# Proc.net
KiCad netlist of a schematic drawn in Altium Designer
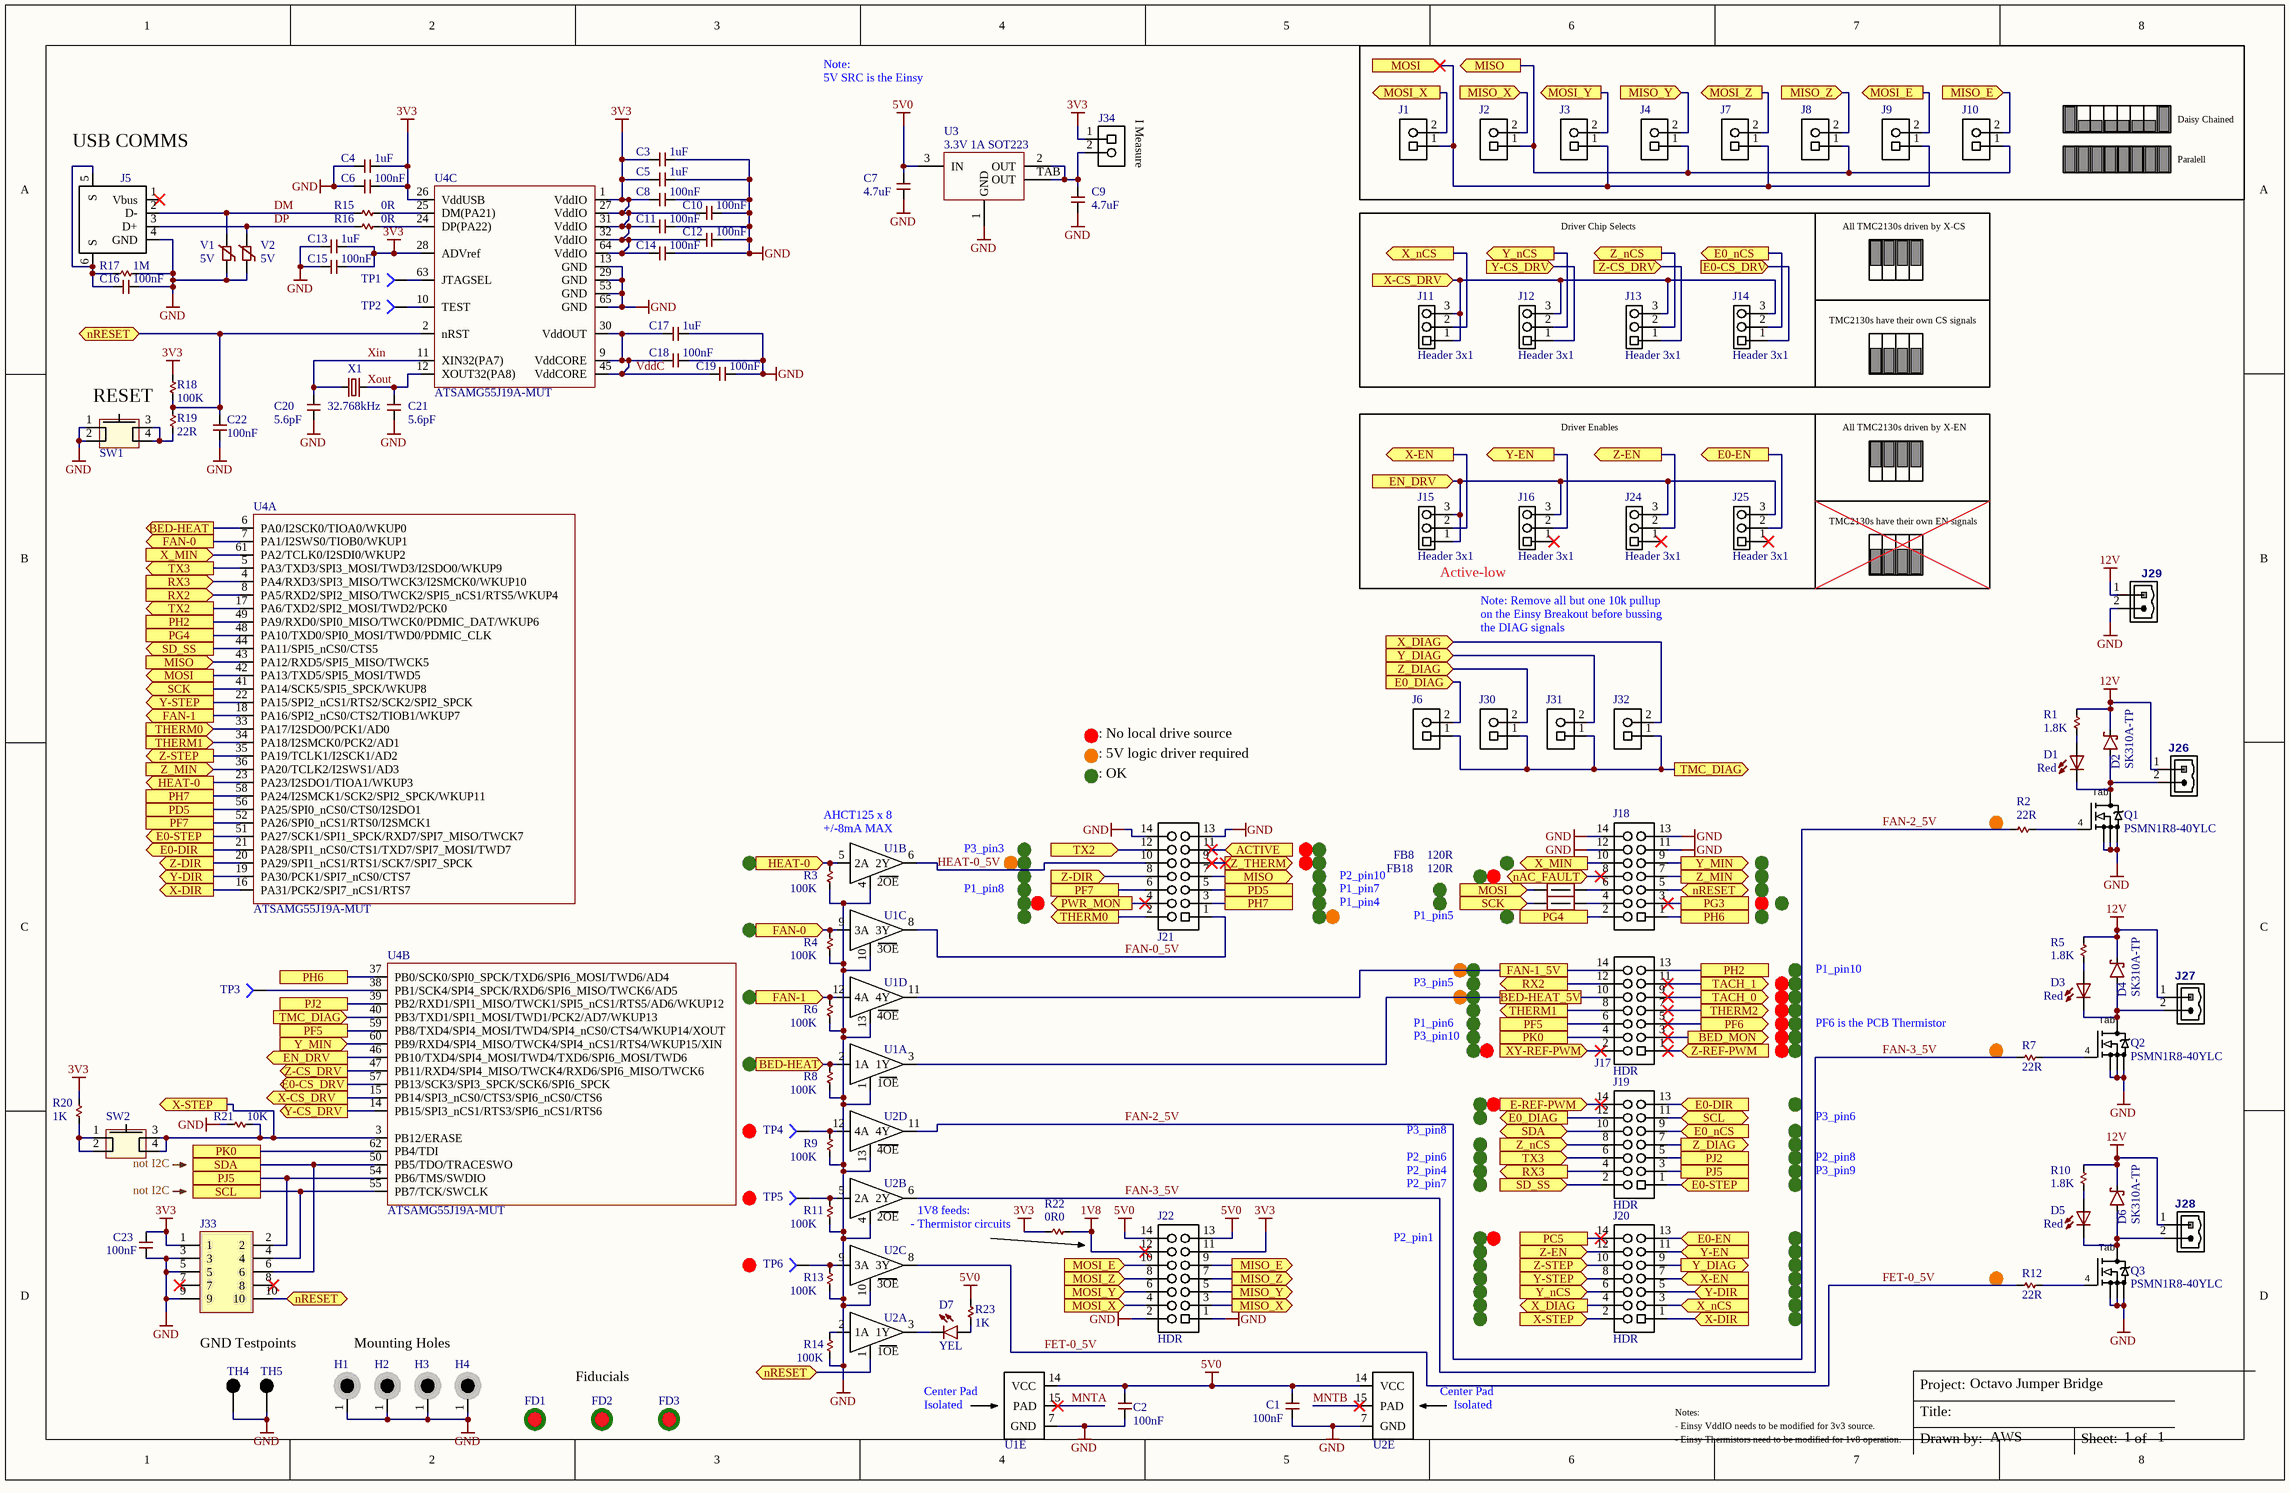
[diagram p0: Proc.SchDoc]

(export (version "E")
  (design (tool "Eeschema 10.0.6"))
  (components
    (comp (ref "C1")
      (value "100nF")
      (footprint "C0603")
      (description "CAP CER 0603 100nF 50V 10% X7R")
      (fields (field (name "MANUFACTURER") "Kemet") (field (name "PART") "100nF 50V X7R 0603"))
      (libsource (lib "Capacitors") (part "100nF 0603 50V X7R"))
    )
    (comp (ref "C2")
      (value "100nF")
      (footprint "C0603")
      (description "CAP CER 0603 100nF 50V 10% X7R")
      (fields (field (name "MANUFACTURER") "Kemet") (field (name "PART") "100nF 50V X7R 0603"))
      (libsource (lib "Capacitors") (part "100nF 0603 50V X7R"))
    )
    (comp (ref "C3")
      (value "1uF")
      (footprint "C0402")
      (description "CAP CER 0402 1uF 6.3V 10% X5R")
      (fields (field (name "MANUFACTURER") "Murata") (field (name "PART") "1uF 6.3V X5R 0402"))
      (libsource (lib "Capacitors") (part "1uF 0402 6.3V X5R"))
    )
    (comp (ref "C4")
      (value "1uF")
      (footprint "C0402")
      (description "CAP CER 0402 1uF 6.3V 10% X5R")
      (fields (field (name "MANUFACTURER") "Murata") (field (name "PART") "1uF 6.3V X5R 0402"))
      (libsource (lib "Capacitors") (part "1uF 0402 6.3V X5R"))
    )
    (comp (ref "C5")
      (value "1uF")
      (footprint "C0402")
      (description "CAP CER 0402 1uF 6.3V 10% X5R")
      (fields (field (name "MANUFACTURER") "Murata") (field (name "PART") "1uF 6.3V X5R 0402"))
      (libsource (lib "Capacitors") (part "1uF 0402 6.3V X5R"))
    )
    (comp (ref "C6")
      (value "100nF")
      (footprint "C0402")
      (description "CAP CER 0402 100nF 16V 10% X7R")
      (fields (field (name "MANUFACTURER") "Murata") (field (name "PART") "0.1uF 16V X7R 0402"))
      (libsource (lib "Capacitors") (part "100nF 0402 16V X7R"))
    )
    (comp (ref "C7")
      (value "4.7uF")
      (footprint "C0603")
      (description "CAP CER 4.7UF 6.3V X7R 0603")
      (fields (field (name "MANUFACTURER") "Samsung") (field (name "TOLERANCE") "10%"))
      (libsource (lib "Capacitors") (part "4.7uF 0603 6.3V X7R"))
    )
    (comp (ref "C8")
      (value "100nF")
      (footprint "C0402")
      (description "CAP CER 0402 100nF 16V 10% X7R")
      (fields (field (name "MANUFACTURER") "Murata") (field (name "PART") "0.1uF 16V X7R 0402"))
      (libsource (lib "Capacitors") (part "100nF 0402 16V X7R"))
    )
    (comp (ref "C9")
      (value "4.7uF")
      (footprint "C0603")
      (description "CAP CER 4.7UF 6.3V X7R 0603")
      (fields (field (name "MANUFACTURER") "Samsung") (field (name "TOLERANCE") "10%"))
      (libsource (lib "Capacitors") (part "4.7uF 0603 6.3V X7R"))
    )
    (comp (ref "C10")
      (value "100nF")
      (footprint "C0402")
      (description "CAP CER 0402 100nF 16V 10% X7R")
      (fields (field (name "MANUFACTURER") "Murata") (field (name "PART") "0.1uF 16V X7R 0402"))
      (libsource (lib "Capacitors") (part "100nF 0402 16V X7R"))
    )
    (comp (ref "C11")
      (value "100nF")
      (footprint "C0402")
      (description "CAP CER 0402 100nF 16V 10% X7R")
      (fields (field (name "MANUFACTURER") "Murata") (field (name "PART") "0.1uF 16V X7R 0402"))
      (libsource (lib "Capacitors") (part "100nF 0402 16V X7R"))
    )
    (comp (ref "C12")
      (value "100nF")
      (footprint "C0402")
      (description "CAP CER 0402 100nF 16V 10% X7R")
      (fields (field (name "MANUFACTURER") "Murata") (field (name "PART") "0.1uF 16V X7R 0402"))
      (libsource (lib "Capacitors") (part "100nF 0402 16V X7R"))
    )
    (comp (ref "C13")
      (value "1uF")
      (footprint "C0402")
      (description "CAP CER 0402 1uF 6.3V 10% X5R")
      (fields (field (name "MANUFACTURER") "Murata") (field (name "PART") "1uF 6.3V X5R 0402"))
      (libsource (lib "Capacitors") (part "1uF 0402 6.3V X5R"))
    )
    (comp (ref "C14")
      (value "100nF")
      (footprint "C0402")
      (description "CAP CER 0402 100nF 16V 10% X7R")
      (fields (field (name "MANUFACTURER") "Murata") (field (name "PART") "0.1uF 16V X7R 0402"))
      (libsource (lib "Capacitors") (part "100nF 0402 16V X7R"))
    )
    (comp (ref "C15")
      (value "100nF")
      (footprint "C0402")
      (description "CAP CER 0402 100nF 16V 10% X7R")
      (fields (field (name "MANUFACTURER") "Murata") (field (name "PART") "0.1uF 16V X7R 0402"))
      (libsource (lib "Capacitors") (part "100nF 0402 16V X7R"))
    )
    (comp (ref "C16")
      (value "100nF")
      (footprint "C0402")
      (description "CAP CER 0402 100nF 16V 10% X7R")
      (fields (field (name "MANUFACTURER") "Murata") (field (name "PART") "0.1uF 16V X7R 0402"))
      (libsource (lib "Capacitors") (part "100nF 0402 16V X7R"))
    )
    (comp (ref "C17")
      (value "1uF")
      (footprint "C0402")
      (description "CAP CER 0402 1uF 6.3V 10% X5R")
      (fields (field (name "MANUFACTURER") "Murata") (field (name "PART") "1uF 6.3V X5R 0402"))
      (libsource (lib "Capacitors") (part "1uF 0402 6.3V X5R"))
    )
    (comp (ref "C18")
      (value "100nF")
      (footprint "C0402")
      (description "CAP CER 0402 100nF 16V 10% X7R")
      (fields (field (name "MANUFACTURER") "Murata") (field (name "PART") "0.1uF 16V X7R 0402"))
      (libsource (lib "Capacitors") (part "100nF 0402 16V X7R"))
    )
    (comp (ref "C19")
      (value "100nF")
      (footprint "C0402")
      (description "CAP CER 0402 100nF 16V 10% X7R")
      (fields (field (name "MANUFACTURER") "Murata") (field (name "PART") "0.1uF 16V X7R 0402"))
      (libsource (lib "Capacitors") (part "100nF 0402 16V X7R"))
    )
    (comp (ref "C20")
      (value "5.6pF")
      (footprint "C0402")
      (description "CAP CER 5.6PF 50V C0G/NP0 0402")
      (fields (field (name "MANUFACTURER") "Murata") (field (name "PART") "5.6pF 50V 0402 C0G"))
      (libsource (lib "Capacitors") (part "5.6pF 50V 0402 C0G"))
    )
    (comp (ref "C21")
      (value "5.6pF")
      (footprint "C0402")
      (description "CAP CER 5.6PF 50V C0G/NP0 0402")
      (fields (field (name "MANUFACTURER") "Murata") (field (name "PART") "5.6pF 50V 0402 C0G"))
      (libsource (lib "Capacitors") (part "5.6pF 50V 0402 C0G"))
    )
    (comp (ref "C22")
      (value "100nF")
      (footprint "C0402")
      (description "CAP CER 0402 100nF 16V 10% X7R")
      (fields (field (name "MANUFACTURER") "Murata") (field (name "PART") "0.1uF 16V X7R 0402"))
      (libsource (lib "Capacitors") (part "100nF 0402 16V X7R"))
    )
    (comp (ref "C23")
      (value "100nF")
      (footprint "C0402")
      (description "CAP CER 0402 100nF 16V 10% X7R")
      (fields (field (name "MANUFACTURER") "Murata") (field (name "PART") "0.1uF 16V X7R 0402"))
      (libsource (lib "Capacitors") (part "100nF 0402 16V X7R"))
    )
    (comp (ref "D1")
      (value "Red")
      (footprint "LED2012120")
      (description "LED 0805 Red")
      (fields (field (name "MANUFACTURER") "Dialight") (field (name "PART") "LED Red 0805"))
      (libsource (lib "LEDs") (part "5988110107F"))
    )
    (comp (ref "D2")
      (value "SK310A-TP")
      (footprint "SMA-SM")
      (description "DIODE Schottky 3A SMA")
      (fields (field (name "MANUFACTURER") "MCC") (field (name "PART") "Schottky Diode 100V 3A"))
      (libsource (lib "Diodes") (part "SK310A"))
    )
    (comp (ref "D3")
      (value "Red")
      (footprint "LED2012120")
      (description "LED 0805 Red")
      (fields (field (name "MANUFACTURER") "Dialight") (field (name "PART") "LED Red 0805"))
      (libsource (lib "LEDs") (part "5988110107F"))
    )
    (comp (ref "D4")
      (value "SK310A-TP")
      (footprint "SMA-SM")
      (description "DIODE Schottky 3A SMA")
      (fields (field (name "MANUFACTURER") "MCC") (field (name "PART") "Schottky Diode 100V 3A"))
      (libsource (lib "Diodes") (part "SK310A"))
    )
    (comp (ref "D5")
      (value "Red")
      (footprint "LED2012120")
      (description "LED 0805 Red")
      (fields (field (name "MANUFACTURER") "Dialight") (field (name "PART") "LED Red 0805"))
      (libsource (lib "LEDs") (part "5988110107F"))
    )
    (comp (ref "D6")
      (value "SK310A-TP")
      (footprint "SMA-SM")
      (description "DIODE Schottky 3A SMA")
      (fields (field (name "MANUFACTURER") "MCC") (field (name "PART") "Schottky Diode 100V 3A"))
      (libsource (lib "Diodes") (part "SK310A"))
    )
    (comp (ref "D7")
      (value "YEL")
      (footprint "LED2012120")
      (description "LED 0805 Yellow")
      (fields (field (name "MANUFACTURER") "Dialight") (field (name "PART") "LED Yellow 0805"))
      (libsource (lib "LEDs") (part "5988140107F"))
    )
    (comp (ref "FB8")
      (value "120R")
      (footprint "R0402")
      (description "FERRITE BEAD 120 OHM 0402 1LN")
      (fields (field (name "MANUFACTURER") "Taiyo Yuden") (field (name "PART") "FERRITE 120R 1A 0402"))
      (libsource (lib "Inductors") (part "FERRITE 120R 1A 0402"))
    )
    (comp (ref "FB18")
      (value "120R")
      (footprint "R0402")
      (description "FERRITE BEAD 120 OHM 0402 1LN")
      (fields (field (name "MANUFACTURER") "Taiyo Yuden") (field (name "PART") "FERRITE 120R 1A 0402"))
      (libsource (lib "Inductors") (part "FERRITE 120R 1A 0402"))
    )
    (comp (ref "FD1")
      (value "FIDUCIAL")
      (footprint "FIDUCIAL-1X2")
      (libsource (lib "MISC") (part "FIDUCIAL"))
    )
    (comp (ref "FD2")
      (value "FIDUCIAL")
      (footprint "FIDUCIAL-1X2")
      (libsource (lib "MISC") (part "FIDUCIAL"))
    )
    (comp (ref "FD3")
      (value "FIDUCIAL")
      (footprint "FIDUCIAL-1X2")
      (libsource (lib "MISC") (part "FIDUCIAL"))
    )
    (comp (ref "H1")
      (value "Hole_DS")
      (footprint "Wave_hole_3x7-doubleSided")
      (libsource (lib "MISC") (part "Hole_DS"))
    )
    (comp (ref "H2")
      (value "Hole_DS")
      (footprint "Wave_hole_3x7-doubleSided")
      (libsource (lib "MISC") (part "Hole_DS"))
    )
    (comp (ref "H3")
      (value "Hole_DS")
      (footprint "Wave_hole_3x7-doubleSided")
      (libsource (lib "MISC") (part "Hole_DS"))
    )
    (comp (ref "H4")
      (value "Hole_DS")
      (footprint "Wave_hole_3x7-doubleSided")
      (libsource (lib "MISC") (part "Hole_DS"))
    )
    (comp (ref "J1")
      (value "Header 2x1")
      (footprint "HDR2X1")
      (description "Header 2Pin 1Row T-Hole")
      (fields (field (name "MANUFACTURER") "Multicomp") (field (name "PART") "CONN 2Pin 1Row 0.1\""))
      (libsource (lib "Connectors") (part "Header 2x1"))
    )
    (comp (ref "J2")
      (value "Header 2x1")
      (footprint "HDR2X1")
      (description "Header 2Pin 1Row T-Hole")
      (fields (field (name "MANUFACTURER") "Multicomp") (field (name "PART") "CONN 2Pin 1Row 0.1\""))
      (libsource (lib "Connectors") (part "Header 2x1"))
    )
    (comp (ref "J3")
      (value "Header 2x1")
      (footprint "HDR2X1")
      (description "Header 2Pin 1Row T-Hole")
      (fields (field (name "MANUFACTURER") "Multicomp") (field (name "PART") "CONN 2Pin 1Row 0.1\""))
      (libsource (lib "Connectors") (part "Header 2x1"))
    )
    (comp (ref "J4")
      (value "Header 2x1")
      (footprint "HDR2X1")
      (description "Header 2Pin 1Row T-Hole")
      (fields (field (name "MANUFACTURER") "Multicomp") (field (name "PART") "CONN 2Pin 1Row 0.1\""))
      (libsource (lib "Connectors") (part "Header 2x1"))
    )
    (comp (ref "J5")
      (value "USB-B TH R/A")
      (footprint "PN61729_ALT")
      (description "USB connector B PTH")
      (fields (field (name "MANUFACTURER") "FCI") (field (name "PART") "USB-B"))
      (libsource (lib "Connectors") (part "USB-B TH R/A"))
    )
    (comp (ref "J6")
      (value "Header 2x1")
      (footprint "HDR2X1")
      (description "Header 2Pin 1Row T-Hole")
      (fields (field (name "MANUFACTURER") "Multicomp") (field (name "PART") "CONN 2Pin 1Row 0.1\""))
      (libsource (lib "Connectors") (part "Header 2x1"))
    )
    (comp (ref "J7")
      (value "Header 2x1")
      (footprint "HDR2X1")
      (description "Header 2Pin 1Row T-Hole")
      (fields (field (name "MANUFACTURER") "Multicomp") (field (name "PART") "CONN 2Pin 1Row 0.1\""))
      (libsource (lib "Connectors") (part "Header 2x1"))
    )
    (comp (ref "J8")
      (value "Header 2x1")
      (footprint "HDR2X1")
      (description "Header 2Pin 1Row T-Hole")
      (fields (field (name "MANUFACTURER") "Multicomp") (field (name "PART") "CONN 2Pin 1Row 0.1\""))
      (libsource (lib "Connectors") (part "Header 2x1"))
    )
    (comp (ref "J9")
      (value "Header 2x1")
      (footprint "HDR2X1")
      (description "Header 2Pin 1Row T-Hole")
      (fields (field (name "MANUFACTURER") "Multicomp") (field (name "PART") "CONN 2Pin 1Row 0.1\""))
      (libsource (lib "Connectors") (part "Header 2x1"))
    )
    (comp (ref "J10")
      (value "Header 2x1")
      (footprint "HDR2X1")
      (description "Header 2Pin 1Row T-Hole")
      (fields (field (name "MANUFACTURER") "Multicomp") (field (name "PART") "CONN 2Pin 1Row 0.1\""))
      (libsource (lib "Connectors") (part "Header 2x1"))
    )
    (comp (ref "J11")
      (value "Header 3x1")
      (footprint "HDR3X1")
      (description "Header 3Pin 1Row T-Hole")
      (fields (field (name "MANUFACTURER") "Multicomp") (field (name "PART") "CONN 3Pin 1Row 0.1\""))
      (libsource (lib "Connectors") (part "Header 3x1 Male Pin"))
    )
    (comp (ref "J12")
      (value "Header 3x1")
      (footprint "HDR3X1")
      (description "Header 3Pin 1Row T-Hole")
      (fields (field (name "MANUFACTURER") "Multicomp") (field (name "PART") "CONN 3Pin 1Row 0.1\""))
      (libsource (lib "Connectors") (part "Header 3x1 Male Pin"))
    )
    (comp (ref "J13")
      (value "Header 3x1")
      (footprint "HDR3X1")
      (description "Header 3Pin 1Row T-Hole")
      (fields (field (name "MANUFACTURER") "Multicomp") (field (name "PART") "CONN 3Pin 1Row 0.1\""))
      (libsource (lib "Connectors") (part "Header 3x1 Male Pin"))
    )
    (comp (ref "J14")
      (value "Header 3x1")
      (footprint "HDR3X1")
      (description "Header 3Pin 1Row T-Hole")
      (fields (field (name "MANUFACTURER") "Multicomp") (field (name "PART") "CONN 3Pin 1Row 0.1\""))
      (libsource (lib "Connectors") (part "Header 3x1 Male Pin"))
    )
    (comp (ref "J15")
      (value "Header 3x1")
      (footprint "HDR3X1")
      (description "Header 3Pin 1Row T-Hole")
      (fields (field (name "MANUFACTURER") "Multicomp") (field (name "PART") "CONN 3Pin 1Row 0.1\""))
      (libsource (lib "Connectors") (part "Header 3x1 Male Pin"))
    )
    (comp (ref "J16")
      (value "Header 3x1")
      (footprint "HDR3X1")
      (description "Header 3Pin 1Row T-Hole")
      (fields (field (name "MANUFACTURER") "Multicomp") (field (name "PART") "CONN 3Pin 1Row 0.1\""))
      (libsource (lib "Connectors") (part "Header 3x1 Male Pin"))
    )
    (comp (ref "J17")
      (value "HDR")
      (footprint "HDR2X7_ALT_PINOUT")
      (description "CONN HEADER .100\" DUAL STR 14POS")
      (fields (field (name "MANUFACTURER") "Sullins") (field (name "TOLERANCE") "-NA-"))
      (libsource (lib "Connectors") (part "Header 2X7 Male Pin"))
    )
    (comp (ref "J18")
      (value "HDR")
      (footprint "HDR2X7_ALT_PINOUT")
      (description "CONN HEADER .100\" DUAL STR 14POS")
      (fields (field (name "MANUFACTURER") "Sullins") (field (name "TOLERANCE") "-NA-"))
      (libsource (lib "Connectors") (part "Header 2X7 Male Pin"))
    )
    (comp (ref "J19")
      (value "HDR")
      (footprint "HDR2X7_ALT_PINOUT")
      (description "CONN HEADER .100\" DUAL STR 14POS")
      (fields (field (name "MANUFACTURER") "Sullins") (field (name "TOLERANCE") "-NA-"))
      (libsource (lib "Connectors") (part "Header 2X7 Male Pin"))
    )
    (comp (ref "J20")
      (value "HDR")
      (footprint "HDR2X7_ALT_PINOUT")
      (description "CONN HEADER .100\" DUAL STR 14POS")
      (fields (field (name "MANUFACTURER") "Sullins") (field (name "TOLERANCE") "-NA-"))
      (libsource (lib "Connectors") (part "Header 2X7 Male Pin"))
    )
    (comp (ref "J21")
      (value "HDR")
      (footprint "HDR2X7_ALT_PINOUT")
      (description "CONN HEADER .100\" DUAL STR 14POS")
      (fields (field (name "MANUFACTURER") "Sullins") (field (name "TOLERANCE") "-NA-"))
      (libsource (lib "Connectors") (part "Header 2X7 Male Pin"))
    )
    (comp (ref "J22")
      (value "HDR")
      (footprint "HDR2X7_ALT_PINOUT")
      (description "CONN HEADER .100\" DUAL STR 14POS")
      (fields (field (name "MANUFACTURER") "Sullins") (field (name "TOLERANCE") "-NA-"))
      (libsource (lib "Connectors") (part "Header 2X7 Male Pin"))
    )
    (comp (ref "J24")
      (value "Header 3x1")
      (footprint "HDR3X1")
      (description "Header 3Pin 1Row T-Hole")
      (fields (field (name "MANUFACTURER") "Multicomp") (field (name "PART") "CONN 3Pin 1Row 0.1\""))
      (libsource (lib "Connectors") (part "Header 3x1 Male Pin"))
    )
    (comp (ref "J25")
      (value "Header 3x1")
      (footprint "HDR3X1")
      (description "Header 3Pin 1Row T-Hole")
      (fields (field (name "MANUFACTURER") "Multicomp") (field (name "PART") "CONN 3Pin 1Row 0.1\""))
      (libsource (lib "Connectors") (part "Header 3x1 Male Pin"))
    )
    (comp (ref "J26")
      (value "0395311002")
      (footprint "MSTBV2")
      (description "Conn - 5.08mm Pitch Fixed")
      (fields (field (name "MANUFACTURER") "Molex") (field (name "PART") "2POS"))
      (libsource (lib "Connectors") (part "0395311002"))
    )
    (comp (ref "J27")
      (value "0395311002")
      (footprint "MSTBV2")
      (description "Conn - 5.08mm Pitch Fixed")
      (fields (field (name "MANUFACTURER") "Molex") (field (name "PART") "2POS"))
      (libsource (lib "Connectors") (part "0395311002"))
    )
    (comp (ref "J28")
      (value "0395311002")
      (footprint "MSTBV2")
      (description "Conn - 5.08mm Pitch Fixed")
      (fields (field (name "MANUFACTURER") "Molex") (field (name "PART") "2POS"))
      (libsource (lib "Connectors") (part "0395311002"))
    )
    (comp (ref "J29")
      (value "0395311002")
      (footprint "MSTBV2")
      (description "Conn - 5.08mm Pitch Fixed")
      (fields (field (name "MANUFACTURER") "Molex") (field (name "PART") "2POS"))
      (libsource (lib "Connectors") (part "0395311002"))
    )
    (comp (ref "J30")
      (value "Header 2x1")
      (footprint "HDR2X1")
      (description "Header 2Pin 1Row T-Hole")
      (fields (field (name "MANUFACTURER") "Multicomp") (field (name "PART") "CONN 2Pin 1Row 0.1\""))
      (libsource (lib "Connectors") (part "Header 2x1"))
    )
    (comp (ref "J31")
      (value "Header 2x1")
      (footprint "HDR2X1")
      (description "Header 2Pin 1Row T-Hole")
      (fields (field (name "MANUFACTURER") "Multicomp") (field (name "PART") "CONN 2Pin 1Row 0.1\""))
      (libsource (lib "Connectors") (part "Header 2x1"))
    )
    (comp (ref "J32")
      (value "Header 2x1")
      (footprint "HDR2X1")
      (description "Header 2Pin 1Row T-Hole")
      (fields (field (name "MANUFACTURER") "Multicomp") (field (name "PART") "CONN 2Pin 1Row 0.1\""))
      (libsource (lib "Connectors") (part "Header 2x1"))
    )
    (comp (ref "J33")
      (value "0.05in 2-Row")
      (footprint "FTSH-105-XX-X-DV")
      (description "20021121-00010C4LF")
      (fields (field (name "MANUFACTURER") "Amphenol FCI") (field (name "PART") "10 Pin Conn 2Row SMT"))
      (libsource (lib "Connectors") (part "ARM Cortex JTAG-DEBUG Header"))
    )
    (comp (ref "J34")
      (value "Header 2x1")
      (footprint "HDR2X1")
      (description "Header 2Pin 1Row T-Hole")
      (fields (field (name "MANUFACTURER") "Multicomp") (field (name "PART") "CONN 2Pin 1Row 0.1\""))
      (libsource (lib "") (part "Header 2x1_1"))
    )
    (comp (ref "Q1")
      (value "PSMN1R8-40YLC")
      (footprint "SOT669")
      (description "MOSFET N-CH 40V 100A LFPAK")
      (fields (field (name "MANUFACTURER") "Nexperia") (field (name "PART") "N-FET"))
      (libsource (lib "Transistors") (part "PSMN1R8-40YLC"))
    )
    (comp (ref "Q2")
      (value "PSMN1R8-40YLC")
      (footprint "SOT669")
      (description "MOSFET N-CH 40V 100A LFPAK")
      (fields (field (name "MANUFACTURER") "Nexperia") (field (name "PART") "N-FET"))
      (libsource (lib "Transistors") (part "PSMN1R8-40YLC"))
    )
    (comp (ref "Q3")
      (value "PSMN1R8-40YLC")
      (footprint "SOT669")
      (description "MOSFET N-CH 40V 100A LFPAK")
      (fields (field (name "MANUFACTURER") "Nexperia") (field (name "PART") "N-FET"))
      (libsource (lib "Transistors") (part "PSMN1R8-40YLC"))
    )
    (comp (ref "R1")
      (value "1.8K")
      (footprint "R0603")
      (description "RES 0603 1.8K 100mW 5%")
      (fields (field (name "MANUFACTURER") "Yageo") (field (name "PART") "1.8k 5% 0603"))
      (libsource (lib "Resistors") (part "1.8k 5% 0603"))
    )
    (comp (ref "R2")
      (value "22R")
      (footprint "R0805")
      (description "RES SMD 22 OHM 1% 1/8W 0805")
      (fields (field (name "MANUFACTURER") "Yageo") (field (name "TOLERANCE") "+/- 1%"))
      (libsource (lib "Resistors") (part "22R 1% 0805"))
    )
    (comp (ref "R3")
      (value "100K")
      (footprint "Passives:R0402")
      (description "RES SMD 100K OHM 1% 1/16W 0402")
      (fields (field (name "MANUFACTURER") "Samsung") (field (name "PART") "100k 1% 0402"))
      (libsource (lib "Resistors") (part "100k 1% 0402"))
    )
    (comp (ref "R4")
      (value "100K")
      (footprint "Passives:R0402")
      (description "RES SMD 100K OHM 1% 1/16W 0402")
      (fields (field (name "MANUFACTURER") "Samsung") (field (name "PART") "100k 1% 0402"))
      (libsource (lib "Resistors") (part "100k 1% 0402"))
    )
    (comp (ref "R5")
      (value "1.8K")
      (footprint "R0603")
      (description "RES 0603 1.8K 100mW 5%")
      (fields (field (name "MANUFACTURER") "Yageo") (field (name "PART") "1.8k 5% 0603"))
      (libsource (lib "Resistors") (part "1.8k 5% 0603"))
    )
    (comp (ref "R6")
      (value "100K")
      (footprint "Passives:R0402")
      (description "RES SMD 100K OHM 1% 1/16W 0402")
      (fields (field (name "MANUFACTURER") "Samsung") (field (name "PART") "100k 1% 0402"))
      (libsource (lib "Resistors") (part "100k 1% 0402"))
    )
    (comp (ref "R7")
      (value "22R")
      (footprint "R0805")
      (description "RES SMD 22 OHM 1% 1/8W 0805")
      (fields (field (name "MANUFACTURER") "Yageo") (field (name "TOLERANCE") "+/- 1%"))
      (libsource (lib "Resistors") (part "22R 1% 0805"))
    )
    (comp (ref "R8")
      (value "100K")
      (footprint "Passives:R0402")
      (description "RES SMD 100K OHM 1% 1/16W 0402")
      (fields (field (name "MANUFACTURER") "Samsung") (field (name "PART") "100k 1% 0402"))
      (libsource (lib "Resistors") (part "100k 1% 0402"))
    )
    (comp (ref "R9")
      (value "100K")
      (footprint "Passives:R0402")
      (description "RES SMD 100K OHM 1% 1/16W 0402")
      (fields (field (name "MANUFACTURER") "Samsung") (field (name "PART") "100k 1% 0402"))
      (libsource (lib "Resistors") (part "100k 1% 0402"))
    )
    (comp (ref "R10")
      (value "1.8K")
      (footprint "R0603")
      (description "RES 0603 1.8K 100mW 5%")
      (fields (field (name "MANUFACTURER") "Yageo") (field (name "PART") "1.8k 5% 0603"))
      (libsource (lib "Resistors") (part "1.8k 5% 0603"))
    )
    (comp (ref "R11")
      (value "100K")
      (footprint "Passives:R0402")
      (description "RES SMD 100K OHM 1% 1/16W 0402")
      (fields (field (name "MANUFACTURER") "Samsung") (field (name "PART") "100k 1% 0402"))
      (libsource (lib "Resistors") (part "100k 1% 0402"))
    )
    (comp (ref "R12")
      (value "22R")
      (footprint "R0805")
      (description "RES SMD 22 OHM 1% 1/8W 0805")
      (fields (field (name "MANUFACTURER") "Yageo") (field (name "TOLERANCE") "+/- 1%"))
      (libsource (lib "Resistors") (part "22R 1% 0805"))
    )
    (comp (ref "R13")
      (value "100K")
      (footprint "Passives:R0402")
      (description "RES SMD 100K OHM 1% 1/16W 0402")
      (fields (field (name "MANUFACTURER") "Samsung") (field (name "PART") "100k 1% 0402"))
      (libsource (lib "Resistors") (part "100k 1% 0402"))
    )
    (comp (ref "R14")
      (value "100K")
      (footprint "Passives:R0402")
      (description "RES SMD 100K OHM 1% 1/16W 0402")
      (fields (field (name "MANUFACTURER") "Samsung") (field (name "PART") "100k 1% 0402"))
      (libsource (lib "Resistors") (part "100k 1% 0402"))
    )
    (comp (ref "R15")
      (value "0R")
      (footprint "R0402")
      (description "RES SMD 0.0OHM JUMPER 1/10W 0402")
      (fields (field (name "MANUFACTURER") "Panasonic") (field (name "TOLERANCE") "1%"))
      (libsource (lib "Resistors") (part "0R 0402"))
    )
    (comp (ref "R16")
      (value "0R")
      (footprint "R0402")
      (description "RES SMD 0.0OHM JUMPER 1/10W 0402")
      (fields (field (name "MANUFACTURER") "Panasonic") (field (name "TOLERANCE") "1%"))
      (libsource (lib "Resistors") (part "0R 0402"))
    )
    (comp (ref "R17")
      (value "1M")
      (footprint "Passives:R0402")
      (description "RES 0402 1M 100mW 5%")
      (fields (field (name "MANUFACTURER") "Panasonic") (field (name "PART") "1M 5% 0402"))
      (libsource (lib "Resistors") (part "1M 5% 0402"))
    )
    (comp (ref "R18")
      (value "100K")
      (footprint "Passives:R0402")
      (description "RES SMD 100K OHM 1% 1/16W 0402")
      (fields (field (name "MANUFACTURER") "Samsung") (field (name "PART") "100k 1% 0402"))
      (libsource (lib "Resistors") (part "100k 1% 0402"))
    )
    (comp (ref "R19")
      (value "22R")
      (footprint "R0805")
      (description "RES SMD 22 OHM 1% 1/8W 0805")
      (fields (field (name "MANUFACTURER") "Yageo") (field (name "TOLERANCE") "+/- 1%"))
      (libsource (lib "Resistors") (part "22R 1% 0805"))
    )
    (comp (ref "R20")
      (value "1K")
      (footprint "R0402")
      (description "RES SMD 1K OHM 1% 1/16W 0402")
      (fields (field (name "MANUFACTURER") "Yageo") (field (name "PART") "1k"))
      (libsource (lib "3Delight") (part "RC0402FR-071KL"))
    )
    (comp (ref "R21")
      (value "10K")
      (footprint "R0402")
      (description "RES SMD 10K OHM 1% 1/16W 0402")
      (fields (field (name "MANUFACTURER") "Yageo") (field (name "PART") "10k 1% 0402"))
      (libsource (lib "Resistors") (part "10k 1% 0402"))
    )
    (comp (ref "R22")
      (value "0R0")
      (footprint "R0805")
      (description "RES 0.0 OHM 1/8W JUMP 0805 SMD")
      (fields (field (name "MANUFACTURER") "STACKPOLE") (field (name "TOLERANCE") "1%"))
      (libsource (lib "Resistors") (part "0R0 1% 0805"))
    )
    (comp (ref "R23")
      (value "1K")
      (footprint "R0402")
      (description "RES SMD 1K OHM 1% 1/16W 0402")
      (fields (field (name "MANUFACTURER") "Yageo") (field (name "PART") "1k"))
      (libsource (lib "3Delight") (part "RC0402FR-071KL"))
    )
    (comp (ref "SW1")
      (value "KMR741NG ULC LFS")
      (footprint "KMR 6 Series")
      (description "SWITCH TACTILE SPST-NO 0.05A 12V")
      (fields (field (name "MANUFACTURER") "C&K") (field (name "PART") "Tactile Pushbutton SMT"))
      (libsource (lib "Switches") (part "KMR741NG ULC LFS"))
    )
    (comp (ref "SW2")
      (value "KMR741NG ULC LFS")
      (footprint "KMR 6 Series")
      (description "SWITCH TACTILE SPST-NO 0.05A 12V")
      (fields (field (name "MANUFACTURER") "C&K") (field (name "PART") "Tactile Pushbutton SMT"))
      (libsource (lib "Switches") (part "KMR741NG ULC LFS"))
    )
    (comp (ref "TH4")
      (value "TH")
      (footprint "TP_80_150")
      (description "THRUHOLE 85mil")
      (fields (field (name "PART") "THRUHOLE"))
      (libsource (lib "Connectors") (part "TH 85mil"))
    )
    (comp (ref "TH5")
      (value "TH")
      (footprint "TP_80_150")
      (description "THRUHOLE 85mil")
      (fields (field (name "PART") "THRUHOLE"))
      (libsource (lib "Connectors") (part "TH 85mil"))
    )
    (comp (ref "TP1")
      (value "NOTAPART-Testpoint")
      (footprint "TP-2")
      (description "Testpoint SMT")
      (libsource (lib "Connectors") (part "Testpoint SMT"))
    )
    (comp (ref "TP2")
      (value "NOTAPART-Testpoint")
      (footprint "TP-2")
      (description "Testpoint SMT")
      (libsource (lib "Connectors") (part "Testpoint SMT"))
    )
    (comp (ref "TP3")
      (value "NOTAPART-Testpoint")
      (footprint "TP-2")
      (description "Testpoint SMT")
      (libsource (lib "Connectors") (part "Testpoint SMT"))
    )
    (comp (ref "TP4")
      (value "NOTAPART-Testpoint")
      (footprint "TP-2")
      (description "Testpoint SMT")
      (libsource (lib "Connectors") (part "Testpoint SMT"))
    )
    (comp (ref "TP5")
      (value "NOTAPART-Testpoint")
      (footprint "TP-2")
      (description "Testpoint SMT")
      (libsource (lib "Connectors") (part "Testpoint SMT"))
    )
    (comp (ref "TP6")
      (value "NOTAPART-Testpoint")
      (footprint "TP-2")
      (description "Testpoint SMT")
      (libsource (lib "Connectors") (part "Testpoint SMT"))
    )
    (comp (ref "U1")
      (value "SN74AHCT125RGYR")
      (footprint "QFN50P350X350X100_RGY_S-PVQFN-N14")
      (description "Quadruple Bus Buffer Gates With 3-State Outputs 14-VQFN -40 to 125")
      (fields
        (field (name "MANUFACTURER") "Texas Instruments")
        (field (name "PART") "IC BUS BUFFER TRI-ST QD 14VQFN")
      )
      (libsource (lib "ICs-Logic") (part "SN74AHCT125"))
    )
    (comp (ref "U2")
      (value "SN74AHCT125RGYR")
      (footprint "QFN50P350X350X100_RGY_S-PVQFN-N14")
      (description "Quadruple Bus Buffer Gates With 3-State Outputs 14-VQFN -40 to 125")
      (fields
        (field (name "MANUFACTURER") "Texas Instruments")
        (field (name "PART") "IC BUS BUFFER TRI-ST QD 14VQFN")
      )
      (libsource (lib "ICs-Logic") (part "SN74AHCT125"))
    )
    (comp (ref "U3")
      (value "3.3V 1A SOT223")
      (footprint "SOT223_AZ1117")
      (description "IC REG LDO 3.3V 1A SOT223")
      (fields (field (name "MANUFACTURER") "Diodes Inc") (field (name "TOLERANCE") "-NA-"))
      (libsource (lib "ICs-Power") (part "LDO 3.3V 1A SOT223"))
    )
    (comp (ref "U4")
      (value "ATSAMG55J19A-MUT")
      (footprint "QFN64_7.5x7.5mm")
      (description "IC MCU 32BIT 512KB FLASH 64QFN")
      (fields (field (name "MANUFACTURER") "Atmel") (field (name "TOLERANCE") "-NA-"))
      (libsource (lib "ICs-uC") (part "ATSAMG55J19A-MUT"))
    )
    (comp (ref "V1")
      (value "5V")
      (footprint "R0603")
      (description "VAR 0603 5V 0.5Pf")
      (fields (field (name "MANUFACTURER") "YAGEO") (field (name "PART") "5VDC"))
      (libsource (lib "ESD") (part "VAR 5V 0603"))
    )
    (comp (ref "V2")
      (value "5V")
      (footprint "R0603")
      (description "VAR 0603 5V 0.5Pf")
      (fields (field (name "MANUFACTURER") "YAGEO") (field (name "PART") "5VDC"))
      (libsource (lib "ESD") (part "VAR 5V 0603"))
    )
    (comp (ref "X1")
      (value "32.768kHz")
      (footprint "XTAL_32X15_2")
      (description "CRYSTAL 32.768KHZ 7PF SMD")
      (fields (field (name "MANUFACTURER") "ECS") (field (name "TOLERANCE") "20ppm"))
      (libsource (lib "XTAL") (part "32.768kHz 20ppm 7pF 50k_ESR"))
    )
  )
  (nets
    (net (code "1") (name "/ACTIVE") (class "Default")
      (node (ref "J21") (pin "11") (pinfunction "11_11") (pintype "passive+no_connect"))
    )
    (net (code "2") (name "/BED-HEAT") (class "Default")
      (node (ref "R8") (pin "1") (pinfunction "1_1") (pintype "passive"))
      (node (ref "U1") (pin "2") (pinfunction "1A_2") (pintype "passive"))
      (node (ref "U4") (pin "6") (pinfunction "PA0/I2SCK0/TIOA0/WKUP0_6") (pintype "passive"))
    )
    (net (code "3") (name "/BED-HEAT_5V") (class "Default")
      (node (ref "J17") (pin "10") (pinfunction "10_10") (pintype "passive"))
      (node (ref "U1") (pin "3") (pinfunction "1Y_3") (pintype "passive"))
    )
    (net (code "4") (name "/BED_MON") (class "Default")
      (node (ref "J17") (pin "3") (pinfunction "3_3") (pintype "passive+no_connect"))
    )
    (net (code "5") (name "/DM") (class "Default")
      (node (ref "J5") (pin "2") (pinfunction "D-_2") (pintype "passive"))
      (node (ref "R15") (pin "1") (pinfunction "1_1") (pintype "passive"))
      (node (ref "V1") (pin "1") (pinfunction "1_1") (pintype "passive"))
    )
    (net (code "6") (name "/DP") (class "Default")
      (node (ref "J5") (pin "3") (pinfunction "D+_3") (pintype "passive"))
      (node (ref "R16") (pin "1") (pinfunction "1_1") (pintype "passive"))
      (node (ref "V2") (pin "1") (pinfunction "1_1") (pintype "passive"))
    )
    (net (code "7") (name "/E-REF-PWM") (class "Default")
      (node (ref "J19") (pin "14") (pinfunction "14_14") (pintype "passive+no_connect"))
    )
    (net (code "8") (name "/E0-CS_DRV") (class "Default")
      (node (ref "J14") (pin "1") (pinfunction "1_1") (pintype "passive"))
      (node (ref "U4") (pin "57") (pinfunction "PB13/SCK3/SPI3_SPCK/SCK6/SPI6_SPCK_57") (pintype "passive"))
    )
    (net (code "9") (name "/E0-DIR") (class "Default")
      (node (ref "J19") (pin "13") (pinfunction "13_13") (pintype "passive"))
      (node (ref "U4") (pin "21") (pinfunction "PA28/SPI1_nCS0/CTS1/TXD7/SPI7_MOSI/TWD7_21") (pintype "passive"))
    )
    (net (code "10") (name "/E0-EN") (class "Default")
      (node (ref "J20") (pin "13") (pinfunction "13_13") (pintype "passive"))
      (node (ref "J25") (pin "2") (pinfunction "2_2") (pintype "passive"))
    )
    (net (code "11") (name "/E0-STEP") (class "Default")
      (node (ref "J19") (pin "1") (pinfunction "1_1") (pintype "passive"))
      (node (ref "U4") (pin "51") (pinfunction "PA27/SCK1/SPI1_SPCK/RXD7/SPI7_MISO/TWCK7_51") (pintype "passive"))
    )
    (net (code "12") (name "/E0_DIAG") (class "Default")
      (node (ref "J19") (pin "12") (pinfunction "12_12") (pintype "passive"))
      (node (ref "J6") (pin "2") (pinfunction "2_2") (pintype "passive"))
    )
    (net (code "13") (name "/E0_nCS") (class "Default")
      (node (ref "J14") (pin "2") (pinfunction "2_2") (pintype "passive"))
      (node (ref "J19") (pin "9") (pinfunction "9_9") (pintype "passive"))
    )
    (net (code "14") (name "/EN_DRV") (class "Default")
      (node (ref "J15") (pin "1") (pinfunction "1_1") (pintype "passive"))
      (node (ref "J15") (pin "3") (pinfunction "3_3") (pintype "passive"))
      (node (ref "J16") (pin "3") (pinfunction "3_3") (pintype "passive"))
      (node (ref "J24") (pin "3") (pinfunction "3_3") (pintype "passive"))
      (node (ref "J25") (pin "3") (pinfunction "3_3") (pintype "passive"))
      (node (ref "U4") (pin "46") (pinfunction "PB10/TXD4/SPI4_MOSI/TWD4/TXD6/SPI6_MOSI/TWD6_46") (pintype "passive"))
    )
    (net (code "15") (name "/FAN-0") (class "Default")
      (node (ref "R4") (pin "1") (pinfunction "1_1") (pintype "passive"))
      (node (ref "U1") (pin "9") (pinfunction "3A_9") (pintype "passive"))
      (node (ref "U4") (pin "7") (pinfunction "PA1/I2SWS0/TIOB0/WKUP1_7") (pintype "passive"))
    )
    (net (code "16") (name "/FAN-0_5V") (class "Default")
      (node (ref "J21") (pin "1") (pinfunction "1_1") (pintype "passive"))
      (node (ref "U1") (pin "8") (pinfunction "3Y_8") (pintype "passive"))
    )
    (net (code "17") (name "/FAN-1") (class "Default")
      (node (ref "R6") (pin "1") (pinfunction "1_1") (pintype "passive"))
      (node (ref "U1") (pin "12") (pinfunction "4A_12") (pintype "passive"))
      (node (ref "U4") (pin "18") (pinfunction "PA16/SPI2_nCS0/CTS2/TIOB1/WKUP7_18") (pintype "passive"))
    )
    (net (code "18") (name "/FAN-1_5V") (class "Default")
      (node (ref "J17") (pin "14") (pinfunction "14_14") (pintype "passive"))
      (node (ref "U1") (pin "11") (pinfunction "4Y_11") (pintype "passive"))
    )
    (net (code "19") (name "/FAN-2_5V") (class "Default")
      (node (ref "R2") (pin "1") (pinfunction "1_1") (pintype "passive"))
      (node (ref "U2") (pin "11") (pinfunction "4Y_11") (pintype "passive"))
    )
    (net (code "20") (name "/FAN-3_5V") (class "Default")
      (node (ref "R7") (pin "1") (pinfunction "1_1") (pintype "passive"))
      (node (ref "U2") (pin "6") (pinfunction "2Y_6") (pintype "passive"))
    )
    (net (code "21") (name "/FET-0_5V") (class "Default")
      (node (ref "R12") (pin "1") (pinfunction "1_1") (pintype "passive"))
      (node (ref "U2") (pin "8") (pinfunction "3Y_8") (pintype "passive"))
    )
    (net (code "22") (name "/HEAT-0") (class "Default")
      (node (ref "R3") (pin "1") (pinfunction "1_1") (pintype "passive"))
      (node (ref "U1") (pin "5") (pinfunction "2A_5") (pintype "passive"))
      (node (ref "U4") (pin "23") (pinfunction "PA23/I2SDO1/TIOA1/WKUP3_23") (pintype "passive"))
    )
    (net (code "23") (name "/HEAT-0_5V") (class "Default")
      (node (ref "J21") (pin "10") (pinfunction "10_10") (pintype "passive"))
      (node (ref "U1") (pin "6") (pinfunction "2Y_6") (pintype "passive"))
    )
    (net (code "24") (name "/MISO") (class "Default")
      (node (ref "J10") (pin "1") (pinfunction "1_1") (pintype "passive"))
      (node (ref "J2") (pin "1") (pinfunction "1_1") (pintype "passive"))
      (node (ref "J21") (pin "7") (pinfunction "7_7") (pintype "passive"))
      (node (ref "J4") (pin "1") (pinfunction "1_1") (pintype "passive"))
      (node (ref "J8") (pin "1") (pinfunction "1_1") (pintype "passive"))
      (node (ref "U4") (pin "43") (pinfunction "PA12/RXD5/SPI5_MISO/TWCK5_43") (pintype "passive"))
    )
    (net (code "25") (name "/MISO_E") (class "Default")
      (node (ref "J10") (pin "2") (pinfunction "2_2") (pintype "passive"))
      (node (ref "J22") (pin "9") (pinfunction "9_9") (pintype "passive"))
    )
    (net (code "26") (name "/MISO_X") (class "Default")
      (node (ref "J2") (pin "2") (pinfunction "2_2") (pintype "passive"))
      (node (ref "J22") (pin "3") (pinfunction "3_3") (pintype "passive"))
    )
    (net (code "27") (name "/MISO_Y") (class "Default")
      (node (ref "J22") (pin "5") (pinfunction "5_5") (pintype "passive"))
      (node (ref "J4") (pin "2") (pinfunction "2_2") (pintype "passive"))
    )
    (net (code "28") (name "/MISO_Z") (class "Default")
      (node (ref "J22") (pin "7") (pinfunction "7_7") (pintype "passive"))
      (node (ref "J8") (pin "2") (pinfunction "2_2") (pintype "passive"))
    )
    (net (code "29") (name "/MNTA") (class "Default")
      (node (ref "U1") (pin "15") (pinfunction "PAD_15") (pintype "passive+no_connect"))
    )
    (net (code "30") (name "/MNTB") (class "Default")
      (node (ref "U2") (pin "15") (pinfunction "PAD_15") (pintype "passive+no_connect"))
    )
    (net (code "31") (name "/MOSI") (class "Default")
      (node (ref "FB8") (pin "2") (pinfunction "2_2") (pintype "passive"))
      (node (ref "J1") (pin "1") (pinfunction "1_1") (pintype "passive"))
      (node (ref "J3") (pin "1") (pinfunction "1_1") (pintype "passive"))
      (node (ref "J7") (pin "1") (pinfunction "1_1") (pintype "passive"))
      (node (ref "J9") (pin "1") (pinfunction "1_1") (pintype "passive"))
      (node (ref "U4") (pin "42") (pinfunction "PA13/TXD5/SPI5_MOSI/TWD5_42") (pintype "passive"))
    )
    (net (code "32") (name "/MOSI_E") (class "Default")
      (node (ref "J22") (pin "10") (pinfunction "10_10") (pintype "passive"))
      (node (ref "J9") (pin "2") (pinfunction "2_2") (pintype "passive"))
    )
    (net (code "33") (name "/MOSI_X") (class "Default")
      (node (ref "J1") (pin "2") (pinfunction "2_2") (pintype "passive"))
      (node (ref "J22") (pin "4") (pinfunction "4_4") (pintype "passive"))
    )
    (net (code "34") (name "/MOSI_Y") (class "Default")
      (node (ref "J22") (pin "6") (pinfunction "6_6") (pintype "passive"))
      (node (ref "J3") (pin "2") (pinfunction "2_2") (pintype "passive"))
    )
    (net (code "35") (name "/MOSI_Z") (class "Default")
      (node (ref "J22") (pin "8") (pinfunction "8_8") (pintype "passive"))
      (node (ref "J7") (pin "2") (pinfunction "2_2") (pintype "passive"))
    )
    (net (code "36") (name "/PC5") (class "Default")
      (node (ref "J20") (pin "14") (pinfunction "14_14") (pintype "passive+no_connect"))
    )
    (net (code "37") (name "/PD5") (class "Default")
      (node (ref "J21") (pin "5") (pinfunction "5_5") (pintype "passive"))
      (node (ref "U4") (pin "56") (pinfunction "PA25/SPI0_nCS0/CTS0/I2SDO1_56") (pintype "passive"))
    )
    (net (code "38") (name "/PF5") (class "Default")
      (node (ref "J17") (pin "6") (pinfunction "6_6") (pintype "passive"))
      (node (ref "U4") (pin "59") (pinfunction "PB8/TXD4/SPI4_MOSI/TWD4/SPI4_nCS0/CTS4/WKUP14/XOUT_59") (pintype "passive"))
    )
    (net (code "39") (name "/PF6") (class "Default")
      (node (ref "J17") (pin "5") (pinfunction "5_5") (pintype "passive+no_connect"))
    )
    (net (code "40") (name "/PF7") (class "Default")
      (node (ref "J21") (pin "6") (pinfunction "6_6") (pintype "passive"))
      (node (ref "U4") (pin "52") (pinfunction "PA26/SPI0_nCS1/RTS0/I2SMCK1_52") (pintype "passive"))
    )
    (net (code "41") (name "/PG3") (class "Default")
      (node (ref "J18") (pin "3") (pinfunction "3_3") (pintype "passive+no_connect"))
    )
    (net (code "42") (name "/PG4") (class "Default")
      (node (ref "J18") (pin "2") (pinfunction "2_2") (pintype "passive"))
      (node (ref "U4") (pin "48") (pinfunction "PA10/TXD0/SPI0_MOSI/TWD0/PDMIC_CLK_48") (pintype "passive"))
    )
    (net (code "43") (name "/PH2") (class "Default")
      (node (ref "J17") (pin "13") (pinfunction "13_13") (pintype "passive"))
      (node (ref "U4") (pin "49") (pinfunction "PA9/RXD0/SPI0_MISO/TWCK0/PDMIC_DAT/WKUP6_49") (pintype "passive"))
    )
    (net (code "44") (name "/PH6") (class "Default")
      (node (ref "J18") (pin "1") (pinfunction "1_1") (pintype "passive"))
      (node (ref "U4") (pin "37") (pinfunction "PB0/SCK0/SPI0_SPCK/TXD6/SPI6_MOSI/TWD6/AD4_37") (pintype "passive"))
    )
    (net (code "45") (name "/PH7") (class "Default")
      (node (ref "J21") (pin "3") (pinfunction "3_3") (pintype "passive"))
      (node (ref "U4") (pin "58") (pinfunction "PA24/I2SMCK1/SCK2/SPI2_SPCK/WKUP11_58") (pintype "passive"))
    )
    (net (code "46") (name "/PJ2") (class "Default")
      (node (ref "J19") (pin "5") (pinfunction "5_5") (pintype "passive"))
      (node (ref "U4") (pin "39") (pinfunction "PB2/RXD1/SPI1_MISO/TWCK1/SPI5_nCS1/RTS5/AD6/WKUP12_39") (pintype "passive"))
    )
    (net (code "47") (name "/PJ5") (class "Default")
      (node (ref "J19") (pin "3") (pinfunction "3_3") (pintype "passive"))
      (node (ref "J33") (pin "2") (pinfunction "2_2") (pintype "passive"))
      (node (ref "U4") (pin "54") (pinfunction "PB6/TMS/SWDIO_54") (pintype "passive"))
    )
    (net (code "48") (name "/PK0") (class "Default")
      (node (ref "J17") (pin "4") (pinfunction "4_4") (pintype "passive"))
      (node (ref "U4") (pin "62") (pinfunction "PB4/TDI_62") (pintype "passive"))
    )
    (net (code "49") (name "/PWR_MON") (class "Default")
      (node (ref "J21") (pin "4") (pinfunction "4_4") (pintype "passive+no_connect"))
    )
    (net (code "50") (name "/RX2") (class "Default")
      (node (ref "J17") (pin "12") (pinfunction "12_12") (pintype "passive"))
      (node (ref "U4") (pin "8") (pinfunction "PA5/RXD2/SPI2_MISO/TWCK2/SPI5_nCS1/RTS5/WKUP4_8") (pintype "passive"))
    )
    (net (code "51") (name "/RX3") (class "Default")
      (node (ref "J19") (pin "4") (pinfunction "4_4") (pintype "passive"))
      (node (ref "U4") (pin "4") (pinfunction "PA4/RXD3/SPI3_MISO/TWCK3/I2SMCK0/WKUP10_4") (pintype "passive"))
    )
    (net (code "52") (name "/SCK") (class "Default")
      (node (ref "FB18") (pin "2") (pinfunction "2_2") (pintype "passive"))
      (node (ref "U4") (pin "41") (pinfunction "PA14/SCK5/SPI5_SPCK/WKUP8_41") (pintype "passive"))
    )
    (net (code "53") (name "/SCL") (class "Default")
      (node (ref "J19") (pin "11") (pinfunction "11_11") (pintype "passive"))
      (node (ref "J33") (pin "4") (pinfunction "4_4") (pintype "passive"))
      (node (ref "U4") (pin "55") (pinfunction "PB7/TCK/SWCLK_55") (pintype "passive"))
    )
    (net (code "54") (name "/SDA") (class "Default")
      (node (ref "J19") (pin "10") (pinfunction "10_10") (pintype "passive"))
      (node (ref "J33") (pin "6") (pinfunction "6_6") (pintype "passive"))
      (node (ref "U4") (pin "50") (pinfunction "PB5/TDO/TRACESWO_50") (pintype "passive"))
    )
    (net (code "55") (name "/SD_SS") (class "Default")
      (node (ref "J19") (pin "2") (pinfunction "2_2") (pintype "passive"))
      (node (ref "U4") (pin "44") (pinfunction "PA11/SPI5_nCS0/CTS5_44") (pintype "passive"))
    )
    (net (code "56") (name "/TACH_0") (class "Default")
      (node (ref "J17") (pin "9") (pinfunction "9_9") (pintype "passive+no_connect"))
    )
    (net (code "57") (name "/TACH_1") (class "Default")
      (node (ref "J17") (pin "11") (pinfunction "11_11") (pintype "passive+no_connect"))
    )
    (net (code "58") (name "/THERM0") (class "Default")
      (node (ref "J21") (pin "2") (pinfunction "2_2") (pintype "passive"))
      (node (ref "U4") (pin "33") (pinfunction "PA17/I2SDO0/PCK1/AD0_33") (pintype "passive"))
    )
    (net (code "59") (name "/THERM1") (class "Default")
      (node (ref "J17") (pin "8") (pinfunction "8_8") (pintype "passive"))
      (node (ref "U4") (pin "34") (pinfunction "PA18/I2SMCK0/PCK2/AD1_34") (pintype "passive"))
    )
    (net (code "60") (name "/THERM2") (class "Default")
      (node (ref "J17") (pin "7") (pinfunction "7_7") (pintype "passive+no_connect"))
    )
    (net (code "61") (name "/TMC_DIAG") (class "Default")
      (node (ref "J30") (pin "1") (pinfunction "1_1") (pintype "passive"))
      (node (ref "J31") (pin "1") (pinfunction "1_1") (pintype "passive"))
      (node (ref "J32") (pin "1") (pinfunction "1_1") (pintype "passive"))
      (node (ref "J6") (pin "1") (pinfunction "1_1") (pintype "passive"))
      (node (ref "U4") (pin "40") (pinfunction "PB3/TXD1/SPI1_MOSI/TWD1/PCK2/AD7/WKUP13_40") (pintype "passive"))
    )
    (net (code "62") (name "/TX2") (class "Default")
      (node (ref "J21") (pin "12") (pinfunction "12_12") (pintype "passive"))
      (node (ref "U4") (pin "17") (pinfunction "PA6/TXD2/SPI2_MOSI/TWD2/PCK0_17") (pintype "passive"))
    )
    (net (code "63") (name "/TX3") (class "Default")
      (node (ref "J19") (pin "6") (pinfunction "6_6") (pintype "passive"))
      (node (ref "U4") (pin "5") (pinfunction "PA3/TXD3/SPI3_MOSI/TWD3/I2SDO0/WKUP9_5") (pintype "passive"))
    )
    (net (code "64") (name "/VddC") (class "Default")
      (node (ref "C17") (pin "2") (pinfunction "2_2") (pintype "passive"))
      (node (ref "C18") (pin "1") (pinfunction "1_1") (pintype "passive"))
      (node (ref "C19") (pin "1") (pinfunction "1_1") (pintype "passive"))
      (node (ref "U4") (pin "30") (pinfunction "VddOUT_30") (pintype "passive"))
      (node (ref "U4") (pin "45") (pinfunction "VddCORE_45") (pintype "passive"))
      (node (ref "U4") (pin "9") (pinfunction "VddCORE_9") (pintype "passive"))
    )
    (net (code "65") (name "/X-CS_DRV") (class "Default")
      (node (ref "J11") (pin "1") (pinfunction "1_1") (pintype "passive"))
      (node (ref "J11") (pin "3") (pinfunction "3_3") (pintype "passive"))
      (node (ref "J12") (pin "3") (pinfunction "3_3") (pintype "passive"))
      (node (ref "J13") (pin "3") (pinfunction "3_3") (pintype "passive"))
      (node (ref "J14") (pin "3") (pinfunction "3_3") (pintype "passive"))
      (node (ref "U4") (pin "15") (pinfunction "PB14/SPI3_nCS0/CTS3/SPI6_nCS0/CTS6_15") (pintype "passive"))
    )
    (net (code "66") (name "/X-DIR") (class "Default")
      (node (ref "J20") (pin "1") (pinfunction "1_1") (pintype "passive"))
      (node (ref "U4") (pin "16") (pinfunction "PA31/PCK2/SPI7_nCS1/RTS7_16") (pintype "passive"))
    )
    (net (code "67") (name "/X-EN") (class "Default")
      (node (ref "J15") (pin "2") (pinfunction "2_2") (pintype "passive"))
      (node (ref "J20") (pin "7") (pinfunction "7_7") (pintype "passive"))
    )
    (net (code "68") (name "/X-STEP") (class "Default")
      (node (ref "J20") (pin "2") (pinfunction "2_2") (pintype "passive"))
      (node (ref "R21") (pin "1") (pinfunction "1_1") (pintype "passive"))
      (node (ref "SW2") (pin "3") (pintype "passive"))
      (node (ref "SW2") (pin "4") (pintype "passive"))
      (node (ref "U4") (pin "3") (pinfunction "PB12/ERASE_3") (pintype "passive"))
    )
    (net (code "69") (name "/XY-REF-PWM") (class "Default")
      (node (ref "J17") (pin "2") (pinfunction "2_2") (pintype "passive+no_connect"))
    )
    (net (code "70") (name "/X_DIAG") (class "Default")
      (node (ref "J20") (pin "4") (pinfunction "4_4") (pintype "passive"))
      (node (ref "J32") (pin "2") (pinfunction "2_2") (pintype "passive"))
    )
    (net (code "71") (name "/X_MIN") (class "Default")
      (node (ref "J18") (pin "10") (pinfunction "10_10") (pintype "passive"))
      (node (ref "U4") (pin "61") (pinfunction "PA2/TCLK0/I2SDI0/WKUP2_61") (pintype "passive"))
    )
    (net (code "72") (name "/X_nCS") (class "Default")
      (node (ref "J11") (pin "2") (pinfunction "2_2") (pintype "passive"))
      (node (ref "J20") (pin "3") (pinfunction "3_3") (pintype "passive"))
    )
    (net (code "73") (name "/Xin") (class "Default")
      (node (ref "C20") (pin "2") (pinfunction "2_2") (pintype "passive"))
      (node (ref "U4") (pin "11") (pinfunction "XIN32(PA7)_11") (pintype "passive"))
      (node (ref "X1") (pin "1") (pinfunction "C1_1") (pintype "passive"))
    )
    (net (code "74") (name "/Xout") (class "Default")
      (node (ref "C21") (pin "2") (pinfunction "2_2") (pintype "passive"))
      (node (ref "U4") (pin "12") (pinfunction "XOUT32(PA8)_12") (pintype "passive"))
      (node (ref "X1") (pin "2") (pinfunction "C2_2") (pintype "passive"))
    )
    (net (code "75") (name "/Y-CS_DRV") (class "Default")
      (node (ref "J12") (pin "1") (pinfunction "1_1") (pintype "passive"))
      (node (ref "U4") (pin "14") (pinfunction "PB15/SPI3_nCS1/RTS3/SPI6_nCS1/RTS6_14") (pintype "passive"))
    )
    (net (code "76") (name "/Y-DIR") (class "Default")
      (node (ref "J20") (pin "5") (pinfunction "5_5") (pintype "passive"))
      (node (ref "U4") (pin "19") (pinfunction "PA30/PCK1/SPI7_nCS0/CTS7_19") (pintype "passive"))
    )
    (net (code "77") (name "/Y-EN") (class "Default")
      (node (ref "J16") (pin "2") (pinfunction "2_2") (pintype "passive"))
      (node (ref "J20") (pin "11") (pinfunction "11_11") (pintype "passive"))
    )
    (net (code "78") (name "/Y-STEP") (class "Default")
      (node (ref "J20") (pin "8") (pinfunction "8_8") (pintype "passive"))
      (node (ref "U4") (pin "22") (pinfunction "PA15/SPI2_nCS1/RTS2/SCK2/SPI2_SPCK_22") (pintype "passive"))
    )
    (net (code "79") (name "/Y_DIAG") (class "Default")
      (node (ref "J20") (pin "9") (pinfunction "9_9") (pintype "passive"))
      (node (ref "J31") (pin "2") (pinfunction "2_2") (pintype "passive"))
    )
    (net (code "80") (name "/Y_MIN") (class "Default")
      (node (ref "J18") (pin "9") (pinfunction "9_9") (pintype "passive"))
      (node (ref "U4") (pin "60") (pinfunction "PB9/RXD4/SPI4_MISO/TWCK4/SPI4_nCS1/RTS4/WKUP15/XIN_60") (pintype "passive"))
    )
    (net (code "81") (name "/Y_nCS") (class "Default")
      (node (ref "J12") (pin "2") (pinfunction "2_2") (pintype "passive"))
      (node (ref "J20") (pin "6") (pinfunction "6_6") (pintype "passive"))
    )
    (net (code "82") (name "/Z-CS_DRV") (class "Default")
      (node (ref "J13") (pin "1") (pinfunction "1_1") (pintype "passive"))
      (node (ref "U4") (pin "47") (pinfunction "PB11/RXD4/SPI4_MISO/TWCK4/RXD6/SPI6_MISO/TWCK6_47") (pintype "passive"))
    )
    (net (code "83") (name "/Z-DIR") (class "Default")
      (node (ref "J21") (pin "8") (pinfunction "8_8") (pintype "passive"))
      (node (ref "U4") (pin "20") (pinfunction "PA29/SPI1_nCS1/RTS1/SCK7/SPI7_SPCK_20") (pintype "passive"))
    )
    (net (code "84") (name "/Z-EN") (class "Default")
      (node (ref "J20") (pin "12") (pinfunction "12_12") (pintype "passive"))
      (node (ref "J24") (pin "2") (pinfunction "2_2") (pintype "passive"))
    )
    (net (code "85") (name "/Z-REF-PWM") (class "Default")
      (node (ref "J17") (pin "1") (pinfunction "1_1") (pintype "passive+no_connect"))
    )
    (net (code "86") (name "/Z-STEP") (class "Default")
      (node (ref "J20") (pin "10") (pinfunction "10_10") (pintype "passive"))
      (node (ref "U4") (pin "35") (pinfunction "PA19/TCLK1/I2SCK1/AD2_35") (pintype "passive"))
    )
    (net (code "87") (name "/Z_DIAG") (class "Default")
      (node (ref "J19") (pin "7") (pinfunction "7_7") (pintype "passive"))
      (node (ref "J30") (pin "2") (pinfunction "2_2") (pintype "passive"))
    )
    (net (code "88") (name "/Z_MIN") (class "Default")
      (node (ref "J18") (pin "7") (pinfunction "7_7") (pintype "passive"))
      (node (ref "U4") (pin "36") (pinfunction "PA20/TCLK2/I2SWS1/AD3_36") (pintype "passive"))
    )
    (net (code "89") (name "/Z_THERM") (class "Default")
      (node (ref "J21") (pin "9") (pinfunction "9_9") (pintype "passive+no_connect"))
    )
    (net (code "90") (name "/Z_nCS") (class "Default")
      (node (ref "J13") (pin "2") (pinfunction "2_2") (pintype "passive"))
      (node (ref "J19") (pin "8") (pinfunction "8_8") (pintype "passive"))
    )
    (net (code "91") (name "/nAC_FAULT") (class "Default")
      (node (ref "J18") (pin "8") (pinfunction "8_8") (pintype "passive+no_connect"))
    )
    (net (code "92") (name "/nRESET") (class "Default")
      (node (ref "C22") (pin "2") (pinfunction "2_2") (pintype "passive"))
      (node (ref "J18") (pin "5") (pinfunction "5_5") (pintype "passive"))
      (node (ref "J33") (pin "10") (pinfunction "10_10") (pintype "passive"))
      (node (ref "R18") (pin "1") (pinfunction "1_1") (pintype "passive"))
      (node (ref "R19") (pin "2") (pinfunction "2_2") (pintype "passive"))
      (node (ref "U2") (pin "1") (pinfunction "1OE_1") (pintype "passive"))
      (node (ref "U4") (pin "2") (pinfunction "nRST_2") (pintype "passive"))
    )
    (net (code "93") (name "1V8") (class "Default")
      (node (ref "J22") (pin "12") (pinfunction "12_12") (pintype "passive"))
      (node (ref "R22") (pin "2") (pinfunction "2_2") (pintype "passive"))
    )
    (net (code "94") (name "3V3") (class "Default")
      (node (ref "C10") (pin "1") (pinfunction "1_1") (pintype "passive"))
      (node (ref "C11") (pin "1") (pinfunction "1_1") (pintype "passive"))
      (node (ref "C12") (pin "1") (pinfunction "1_1") (pintype "passive"))
      (node (ref "C13") (pin "1") (pinfunction "1_1") (pintype "passive"))
      (node (ref "C14") (pin "1") (pinfunction "1_1") (pintype "passive"))
      (node (ref "C15") (pin "2") (pinfunction "2_2") (pintype "passive"))
      (node (ref "C23") (pin "1") (pinfunction "1_1") (pintype "passive"))
      (node (ref "C3") (pin "2") (pinfunction "2_2") (pintype "passive"))
      (node (ref "C4") (pin "1") (pinfunction "1_1") (pintype "passive"))
      (node (ref "C5") (pin "2") (pinfunction "2_2") (pintype "passive"))
      (node (ref "C6") (pin "2") (pinfunction "2_2") (pintype "passive"))
      (node (ref "C8") (pin "1") (pinfunction "1_1") (pintype "passive"))
      (node (ref "J22") (pin "11") (pinfunction "11_11") (pintype "passive"))
      (node (ref "J33") (pin "1") (pinfunction "1_1") (pintype "passive"))
      (node (ref "J34") (pin "1") (pinfunction "1_1") (pintype "passive"))
      (node (ref "R18") (pin "2") (pinfunction "2_2") (pintype "passive"))
      (node (ref "R20") (pin "2") (pinfunction "2_2") (pintype "passive"))
      (node (ref "R22") (pin "1") (pinfunction "1_1") (pintype "passive"))
      (node (ref "U4") (pin "1") (pinfunction "VddIO_1") (pintype "passive"))
      (node (ref "U4") (pin "26") (pinfunction "VddUSB_26") (pintype "passive"))
      (node (ref "U4") (pin "27") (pinfunction "VddIO_27") (pintype "passive"))
      (node (ref "U4") (pin "28") (pinfunction "ADVref_28") (pintype "passive"))
      (node (ref "U4") (pin "31") (pinfunction "VddIO_31") (pintype "passive"))
      (node (ref "U4") (pin "32") (pinfunction "VddIO_32") (pintype "passive"))
      (node (ref "U4") (pin "64") (pinfunction "VddIO_64") (pintype "passive"))
    )
    (net (code "95") (name "5V0") (class "Default")
      (node (ref "C1") (pin "2") (pinfunction "2_2") (pintype "passive"))
      (node (ref "C2") (pin "2") (pinfunction "2_2") (pintype "passive"))
      (node (ref "C7") (pin "2") (pinfunction "2_2") (pintype "passive"))
      (node (ref "J22") (pin "13") (pinfunction "13_13") (pintype "passive"))
      (node (ref "J22") (pin "14") (pinfunction "14_14") (pintype "passive"))
      (node (ref "R23") (pin "1") (pinfunction "1_1") (pintype "passive"))
      (node (ref "U1") (pin "14") (pinfunction "VCC_14") (pintype "passive"))
      (node (ref "U2") (pin "14") (pinfunction "VCC_14") (pintype "passive"))
      (node (ref "U3") (pin "3") (pinfunction "IN_3") (pintype "power_in"))
    )
    (net (code "96") (name "12V") (class "Default")
      (node (ref "D2") (pin "K") (pinfunction "K_K") (pintype "passive"))
      (node (ref "D4") (pin "K") (pinfunction "K_K") (pintype "passive"))
      (node (ref "D6") (pin "K") (pinfunction "K_K") (pintype "passive"))
      (node (ref "J26") (pin "1") (pinfunction "1_1") (pintype "passive"))
      (node (ref "J27") (pin "1") (pinfunction "1_1") (pintype "passive"))
      (node (ref "J28") (pin "1") (pinfunction "1_1") (pintype "passive"))
      (node (ref "J29") (pin "1") (pinfunction "1_1") (pintype "passive"))
      (node (ref "R1") (pin "2") (pinfunction "2_2") (pintype "passive"))
      (node (ref "R10") (pin "2") (pinfunction "2_2") (pintype "passive"))
      (node (ref "R5") (pin "2") (pinfunction "2_2") (pintype "passive"))
    )
    (net (code "97") (name "GND") (class "Default")
      (node (ref "C1") (pin "1") (pinfunction "1_1") (pintype "passive"))
      (node (ref "C10") (pin "2") (pinfunction "2_2") (pintype "passive"))
      (node (ref "C11") (pin "2") (pinfunction "2_2") (pintype "passive"))
      (node (ref "C12") (pin "2") (pinfunction "2_2") (pintype "passive"))
      (node (ref "C13") (pin "2") (pinfunction "2_2") (pintype "passive"))
      (node (ref "C14") (pin "2") (pinfunction "2_2") (pintype "passive"))
      (node (ref "C15") (pin "1") (pinfunction "1_1") (pintype "passive"))
      (node (ref "C16") (pin "1") (pinfunction "1_1") (pintype "passive"))
      (node (ref "C17") (pin "1") (pinfunction "1_1") (pintype "passive"))
      (node (ref "C18") (pin "2") (pinfunction "2_2") (pintype "passive"))
      (node (ref "C19") (pin "2") (pinfunction "2_2") (pintype "passive"))
      (node (ref "C2") (pin "1") (pinfunction "1_1") (pintype "passive"))
      (node (ref "C20") (pin "1") (pinfunction "1_1") (pintype "passive"))
      (node (ref "C21") (pin "1") (pinfunction "1_1") (pintype "passive"))
      (node (ref "C22") (pin "1") (pinfunction "1_1") (pintype "passive"))
      (node (ref "C23") (pin "2") (pinfunction "2_2") (pintype "passive"))
      (node (ref "C3") (pin "1") (pinfunction "1_1") (pintype "passive"))
      (node (ref "C4") (pin "2") (pinfunction "2_2") (pintype "passive"))
      (node (ref "C5") (pin "1") (pinfunction "1_1") (pintype "passive"))
      (node (ref "C6") (pin "1") (pinfunction "1_1") (pintype "passive"))
      (node (ref "C7") (pin "1") (pinfunction "1_1") (pintype "passive"))
      (node (ref "C8") (pin "2") (pinfunction "2_2") (pintype "passive"))
      (node (ref "C9") (pin "1") (pinfunction "1_1") (pintype "passive"))
      (node (ref "H1") (pin "1") (pinfunction "1_1") (pintype "power_in"))
      (node (ref "H2") (pin "1") (pinfunction "1_1") (pintype "power_in"))
      (node (ref "H3") (pin "1") (pinfunction "1_1") (pintype "power_in"))
      (node (ref "H4") (pin "1") (pinfunction "1_1") (pintype "power_in"))
      (node (ref "J18") (pin "11") (pinfunction "11_11") (pintype "passive"))
      (node (ref "J18") (pin "12") (pinfunction "12_12") (pintype "passive"))
      (node (ref "J18") (pin "13") (pinfunction "13_13") (pintype "passive"))
      (node (ref "J18") (pin "14") (pinfunction "14_14") (pintype "passive"))
      (node (ref "J21") (pin "13") (pinfunction "13_13") (pintype "passive"))
      (node (ref "J21") (pin "14") (pinfunction "14_14") (pintype "passive"))
      (node (ref "J22") (pin "1") (pinfunction "1_1") (pintype "passive"))
      (node (ref "J22") (pin "2") (pinfunction "2_2") (pintype "passive"))
      (node (ref "J29") (pin "2") (pinfunction "2_2") (pintype "passive"))
      (node (ref "J33") (pin "3") (pinfunction "3_3") (pintype "passive"))
      (node (ref "J33") (pin "5") (pinfunction "5_5") (pintype "passive"))
      (node (ref "J33") (pin "9") (pinfunction "9_9") (pintype "passive"))
      (node (ref "J5") (pin "4") (pinfunction "GND_4") (pintype "passive"))
      (node (ref "Q1") (pin "1") (pinfunction "S_1") (pintype "passive"))
      (node (ref "Q1") (pin "2") (pinfunction "S_2") (pintype "passive"))
      (node (ref "Q1") (pin "3") (pinfunction "S_3") (pintype "passive"))
      (node (ref "Q2") (pin "1") (pinfunction "S_1") (pintype "passive"))
      (node (ref "Q2") (pin "2") (pinfunction "S_2") (pintype "passive"))
      (node (ref "Q2") (pin "3") (pinfunction "S_3") (pintype "passive"))
      (node (ref "Q3") (pin "1") (pinfunction "S_1") (pintype "passive"))
      (node (ref "Q3") (pin "2") (pinfunction "S_2") (pintype "passive"))
      (node (ref "Q3") (pin "3") (pinfunction "S_3") (pintype "passive"))
      (node (ref "R11") (pin "2") (pinfunction "2_2") (pintype "passive"))
      (node (ref "R13") (pin "2") (pinfunction "2_2") (pintype "passive"))
      (node (ref "R14") (pin "2") (pinfunction "2_2") (pintype "passive"))
      (node (ref "R17") (pin "1") (pinfunction "1_1") (pintype "passive"))
      (node (ref "R21") (pin "2") (pinfunction "2_2") (pintype "passive"))
      (node (ref "R3") (pin "2") (pinfunction "2_2") (pintype "passive"))
      (node (ref "R4") (pin "2") (pinfunction "2_2") (pintype "passive"))
      (node (ref "R6") (pin "2") (pinfunction "2_2") (pintype "passive"))
      (node (ref "R8") (pin "2") (pinfunction "2_2") (pintype "passive"))
      (node (ref "R9") (pin "2") (pinfunction "2_2") (pintype "passive"))
      (node (ref "SW1") (pin "1") (pintype "passive"))
      (node (ref "SW1") (pin "2") (pintype "passive"))
      (node (ref "TH4") (pin "1") (pinfunction "1_1") (pintype "passive"))
      (node (ref "TH5") (pin "1") (pinfunction "1_1") (pintype "passive"))
      (node (ref "U1") (pin "1") (pinfunction "1OE_1") (pintype "passive"))
      (node (ref "U1") (pin "10") (pinfunction "3OE_10") (pintype "passive"))
      (node (ref "U1") (pin "13") (pinfunction "4OE_13") (pintype "passive"))
      (node (ref "U1") (pin "4") (pinfunction "2OE_4") (pintype "passive"))
      (node (ref "U1") (pin "7") (pinfunction "GND_7") (pintype "passive"))
      (node (ref "U2") (pin "10") (pinfunction "3OE_10") (pintype "passive"))
      (node (ref "U2") (pin "13") (pinfunction "4OE_13") (pintype "passive"))
      (node (ref "U2") (pin "4") (pinfunction "2OE_4") (pintype "passive"))
      (node (ref "U2") (pin "7") (pinfunction "GND_7") (pintype "passive"))
      (node (ref "U3") (pin "1") (pinfunction "GND_1") (pintype "power_in"))
      (node (ref "U4") (pin "13") (pinfunction "GND_13") (pintype "passive"))
      (node (ref "U4") (pin "29") (pinfunction "GND_29") (pintype "passive"))
      (node (ref "U4") (pin "53") (pinfunction "GND_53") (pintype "passive"))
      (node (ref "U4") (pin "65") (pinfunction "GND_65") (pintype "passive"))
      (node (ref "V1") (pin "2") (pinfunction "2_2") (pintype "passive"))
      (node (ref "V2") (pin "2") (pinfunction "2_2") (pintype "passive"))
    )
    (net (code "98") (name "Net-(C9-Pad2)") (class "Default")
      (node (ref "C9") (pin "2") (pinfunction "2_2") (pintype "passive"))
      (node (ref "J34") (pin "2") (pinfunction "2_2") (pintype "passive"))
      (node (ref "U3") (pin "2") (pinfunction "OUT_2") (pintype "power_in"))
      (node (ref "U3") (pin "TAB") (pinfunction "OUT_TAB") (pintype "power_in"))
    )
    (net (code "99") (name "Net-(C16-Pad2)") (class "Default")
      (node (ref "C16") (pin "2") (pinfunction "2_2") (pintype "passive"))
      (node (ref "J5") (pin "5") (pinfunction "S_5") (pintype "passive"))
      (node (ref "J5") (pin "6") (pinfunction "S_6") (pintype "passive"))
      (node (ref "R17") (pin "2") (pinfunction "2_2") (pintype "passive"))
    )
    (net (code "100") (name "Net-(D1-PadA)") (class "Default")
      (node (ref "D1") (pin "A") (pinfunction "A_A") (pintype "passive"))
      (node (ref "R1") (pin "1") (pinfunction "1_1") (pintype "passive"))
    )
    (net (code "101") (name "Net-(D3-PadA)") (class "Default")
      (node (ref "D3") (pin "A") (pinfunction "A_A") (pintype "passive"))
      (node (ref "R5") (pin "1") (pinfunction "1_1") (pintype "passive"))
    )
    (net (code "102") (name "Net-(D5-PadA)") (class "Default")
      (node (ref "D5") (pin "A") (pinfunction "A_A") (pintype "passive"))
      (node (ref "R10") (pin "1") (pinfunction "1_1") (pintype "passive"))
    )
    (net (code "103") (name "Net-(D7-PadA)") (class "Default")
      (node (ref "D7") (pin "A") (pinfunction "A_A") (pintype "passive"))
      (node (ref "R23") (pin "2") (pinfunction "2_2") (pintype "passive"))
    )
    (net (code "104") (name "Net-(FB8-Pad1)") (class "Default")
      (node (ref "FB8") (pin "1") (pinfunction "1_1") (pintype "passive"))
      (node (ref "J18") (pin "6") (pinfunction "6_6") (pintype "passive"))
    )
    (net (code "105") (name "Net-(FB18-Pad1)") (class "Default")
      (node (ref "FB18") (pin "1") (pinfunction "1_1") (pintype "passive"))
      (node (ref "J18") (pin "4") (pinfunction "4_4") (pintype "passive"))
    )
    (net (code "106") (name "Net-(Q1-D)") (class "Default")
      (node (ref "D1") (pin "C") (pinfunction "C_C") (pintype "passive"))
      (node (ref "D2") (pin "A") (pinfunction "A_A") (pintype "passive"))
      (node (ref "J26") (pin "2") (pinfunction "2_2") (pintype "passive"))
      (node (ref "Q1") (pin "TAB") (pinfunction "D_TAB") (pintype "passive"))
    )
    (net (code "107") (name "Net-(Q1-G)") (class "Default")
      (node (ref "Q1") (pin "4") (pinfunction "G_4") (pintype "passive"))
      (node (ref "R2") (pin "2") (pinfunction "2_2") (pintype "passive"))
    )
    (net (code "108") (name "Net-(Q2-D)") (class "Default")
      (node (ref "D3") (pin "C") (pinfunction "C_C") (pintype "passive"))
      (node (ref "D4") (pin "A") (pinfunction "A_A") (pintype "passive"))
      (node (ref "J27") (pin "2") (pinfunction "2_2") (pintype "passive"))
      (node (ref "Q2") (pin "TAB") (pinfunction "D_TAB") (pintype "passive"))
    )
    (net (code "109") (name "Net-(Q2-G)") (class "Default")
      (node (ref "Q2") (pin "4") (pinfunction "G_4") (pintype "passive"))
      (node (ref "R7") (pin "2") (pinfunction "2_2") (pintype "passive"))
    )
    (net (code "110") (name "Net-(Q3-D)") (class "Default")
      (node (ref "D5") (pin "C") (pinfunction "C_C") (pintype "passive"))
      (node (ref "D6") (pin "A") (pinfunction "A_A") (pintype "passive"))
      (node (ref "J28") (pin "2") (pinfunction "2_2") (pintype "passive"))
      (node (ref "Q3") (pin "TAB") (pinfunction "D_TAB") (pintype "passive"))
    )
    (net (code "111") (name "Net-(Q3-G)") (class "Default")
      (node (ref "Q3") (pin "4") (pinfunction "G_4") (pintype "passive"))
      (node (ref "R12") (pin "2") (pinfunction "2_2") (pintype "passive"))
    )
    (net (code "112") (name "Net-(R19-Pad1)") (class "Default")
      (node (ref "R19") (pin "1") (pinfunction "1_1") (pintype "passive"))
      (node (ref "SW1") (pin "3") (pintype "passive"))
      (node (ref "SW1") (pin "4") (pintype "passive"))
    )
    (net (code "113") (name "Net-(R20-Pad1)") (class "Default")
      (node (ref "R20") (pin "1") (pinfunction "1_1") (pintype "passive"))
      (node (ref "SW2") (pin "1") (pintype "passive"))
      (node (ref "SW2") (pin "2") (pintype "passive"))
    )
    (net (code "114") (name "Net-(U2A-1A)") (class "Default")
      (node (ref "R14") (pin "1") (pinfunction "1_1") (pintype "passive"))
      (node (ref "U2") (pin "2") (pinfunction "1A_2") (pintype "passive"))
    )
    (net (code "115") (name "Net-(U2A-1Y)") (class "Default")
      (node (ref "D7") (pin "C") (pinfunction "C_C") (pintype "passive"))
      (node (ref "U2") (pin "3") (pinfunction "1Y_3") (pintype "passive"))
    )
    (net (code "116") (name "Net-(U2B-2A)") (class "Default")
      (node (ref "R11") (pin "1") (pinfunction "1_1") (pintype "passive"))
      (node (ref "TP5") (pin "1") (pinfunction "1_1") (pintype "passive"))
      (node (ref "U2") (pin "5") (pinfunction "2A_5") (pintype "passive"))
    )
    (net (code "117") (name "Net-(U2C-3A)") (class "Default")
      (node (ref "R13") (pin "1") (pinfunction "1_1") (pintype "passive"))
      (node (ref "TP6") (pin "1") (pinfunction "1_1") (pintype "passive"))
      (node (ref "U2") (pin "9") (pinfunction "3A_9") (pintype "passive"))
    )
    (net (code "118") (name "Net-(U2D-4A)") (class "Default")
      (node (ref "R9") (pin "1") (pinfunction "1_1") (pintype "passive"))
      (node (ref "TP4") (pin "1") (pinfunction "1_1") (pintype "passive"))
      (node (ref "U2") (pin "12") (pinfunction "4A_12") (pintype "passive"))
    )
    (net (code "119") (name "Net-(U4B-PB1{slash}SCK4{slash}SPI4_SPCK{slash}RXD6{slash}SPI6_MISO{slash}TWCK6{slash}AD5)") (class "Default")
      (node (ref "TP3") (pin "1") (pinfunction "1_1") (pintype "passive"))
      (node (ref "U4") (pin "38") (pinfunction "PB1/SCK4/SPI4_SPCK/RXD6/SPI6_MISO/TWCK6/AD5_38") (pintype "passive"))
    )
    (net (code "120") (name "Net-(U4C-DM(PA21))") (class "Default")
      (node (ref "R15") (pin "2") (pinfunction "2_2") (pintype "passive"))
      (node (ref "U4") (pin "25") (pinfunction "DM(PA21)_25") (pintype "passive"))
    )
    (net (code "121") (name "Net-(U4C-DP(PA22))") (class "Default")
      (node (ref "R16") (pin "2") (pinfunction "2_2") (pintype "passive"))
      (node (ref "U4") (pin "24") (pinfunction "DP(PA22)_24") (pintype "passive"))
    )
    (net (code "122") (name "Net-(U4C-JTAGSEL)") (class "Default")
      (node (ref "TP1") (pin "1") (pinfunction "1_1") (pintype "passive"))
      (node (ref "U4") (pin "63") (pinfunction "JTAGSEL_63") (pintype "passive"))
    )
    (net (code "123") (name "Net-(U4C-TEST)") (class "Default")
      (node (ref "TP2") (pin "1") (pinfunction "1_1") (pintype "passive"))
      (node (ref "U4") (pin "10") (pinfunction "TEST_10") (pintype "passive"))
    )
    (net (code "124") (name "unconnected-(J5-Vbus-Pad1)") (class "Default")
      (node (ref "J5") (pin "1") (pinfunction "Vbus_1") (pintype "passive+no_connect"))
    )
    (net (code "125") (name "unconnected-(J16-Pad1)") (class "Default")
      (node (ref "J16") (pin "1") (pinfunction "1_1") (pintype "passive+no_connect"))
    )
    (net (code "126") (name "unconnected-(J24-Pad1)") (class "Default")
      (node (ref "J24") (pin "1") (pinfunction "1_1") (pintype "passive+no_connect"))
    )
    (net (code "127") (name "unconnected-(J25-Pad1)") (class "Default")
      (node (ref "J25") (pin "1") (pinfunction "1_1") (pintype "passive+no_connect"))
    )
    (net (code "128") (name "unconnected-(J33-Pad7)") (class "Default")
      (node (ref "J33") (pin "7") (pinfunction "7_7") (pintype "passive+no_connect"))
    )
    (net (code "129") (name "unconnected-(J33-Pad8)") (class "Default")
      (node (ref "J33") (pin "8") (pinfunction "8_8") (pintype "passive+no_connect"))
    )
  )
)
